# cam_switch_nobec.net
KiCad netlist of a schematic drawn in EAGLE
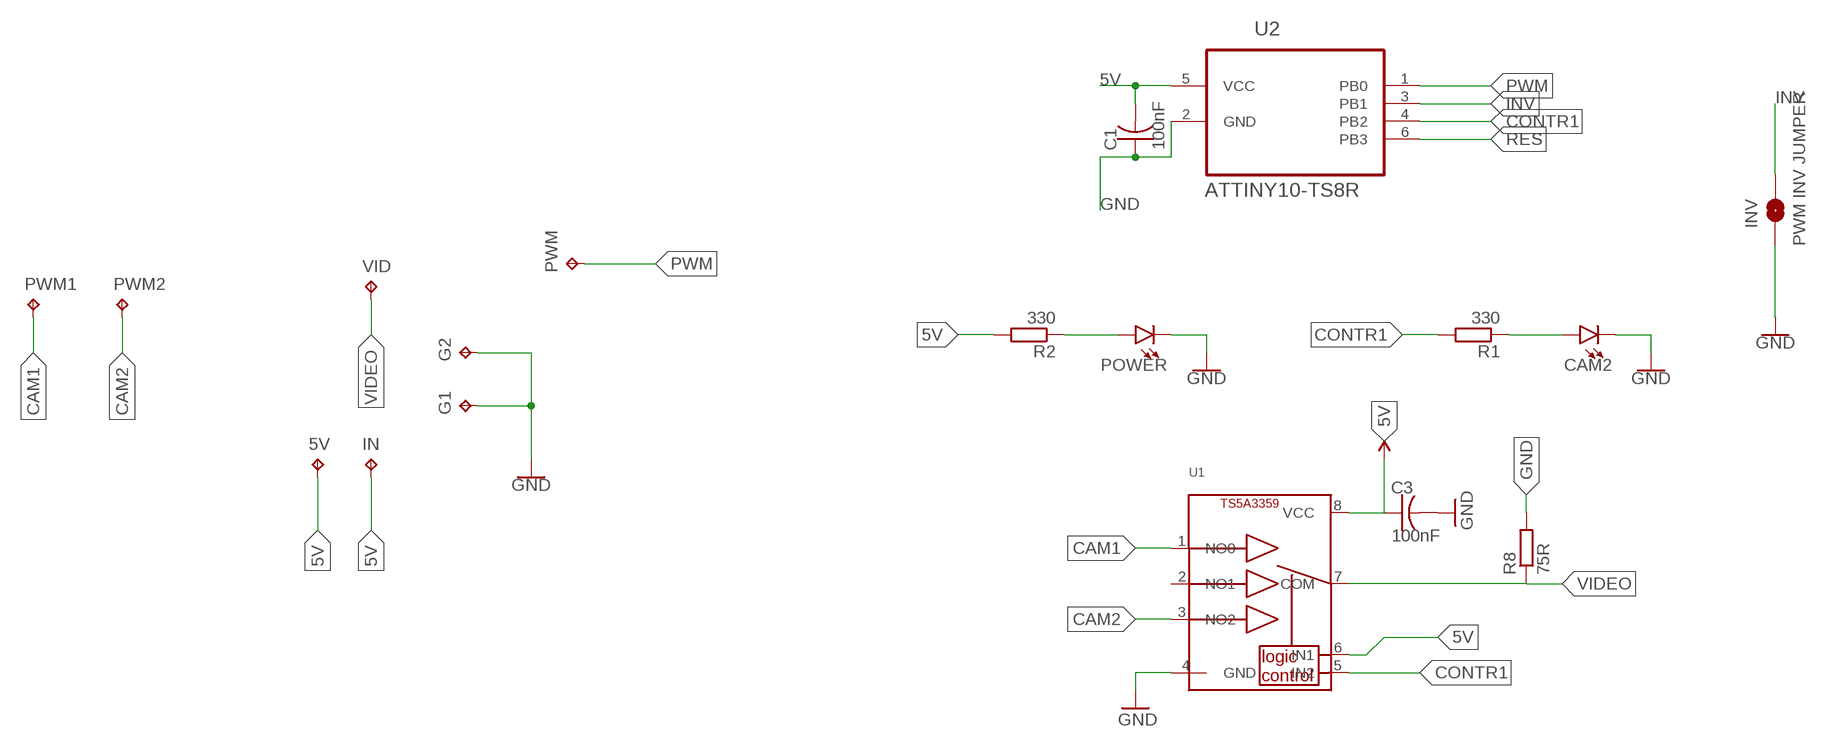
[diagram p0: schematic, sheet 1]

(export (version "E")
  (design (tool "Eeschema 10.0.6"))
  (components
    (comp (ref "5V")
      (value "TPTP20SQ")
      (footprint "eagle-import:TP20SQ")
      (libsource (lib "eagle-import") (part "TPTP20SQ"))
    )
    (comp (ref "C1")
      (value "100nF")
      (footprint "eagle-import:C0603")
      (libsource (lib "eagle-import") (part "C-USC0603"))
    )
    (comp (ref "C3")
      (value "100nF")
      (footprint "eagle-import:C0603")
      (libsource (lib "eagle-import") (part "C-USC0603"))
    )
    (comp (ref "CAM2")
      (value "LED0603")
      (footprint "eagle-import:LED-0603")
      (libsource (lib "eagle-import") (part "LED0603"))
    )
    (comp (ref "G1")
      (value "TPTP20SQ")
      (footprint "eagle-import:TP20SQ")
      (libsource (lib "eagle-import") (part "TPTP20SQ"))
    )
    (comp (ref "G2")
      (value "TPTP20SQ")
      (footprint "eagle-import:TP20SQ")
      (libsource (lib "eagle-import") (part "TPTP20SQ"))
    )
    (comp (ref "IN")
      (value "TPTP20SQ")
      (footprint "eagle-import:TP20SQ")
      (libsource (lib "eagle-import") (part "TPTP20SQ"))
    )
    (comp (ref "INV")
      (value "PWM INV JUMPER")
      (footprint "eagle-import:SMT-JUMPER_2_NO_NO-SILK")
      (libsource (lib "eagle-import") (part "JUMPER-SMT_2_NO_NO-SILK"))
    )
    (comp (ref "POWER")
      (value "LED0603")
      (footprint "eagle-import:LED-0603")
      (libsource (lib "eagle-import") (part "LED0603"))
    )
    (comp (ref "PWM")
      (value "TPTP20SQ")
      (footprint "eagle-import:TP20SQ")
      (libsource (lib "eagle-import") (part "TPTP20SQ"))
    )
    (comp (ref "PWM1")
      (value "TPTP20SQ")
      (footprint "eagle-import:TP20SQ")
      (libsource (lib "eagle-import") (part "TPTP20SQ"))
    )
    (comp (ref "PWM2")
      (value "TPTP20SQ")
      (footprint "eagle-import:TP20SQ")
      (libsource (lib "eagle-import") (part "TPTP20SQ"))
    )
    (comp (ref "R1")
      (value "330")
      (footprint "eagle-import:R0603")
      (libsource (lib "eagle-import") (part "R-EU_R0603"))
    )
    (comp (ref "R2")
      (value "330")
      (footprint "eagle-import:R0603")
      (libsource (lib "eagle-import") (part "R-EU_R0603"))
    )
    (comp (ref "R8")
      (value "75R")
      (footprint "eagle-import:R0603")
      (libsource (lib "eagle-import") (part "R-EU_R0603"))
    )
    (comp (ref "U1")
      (value "TS5A3359")
      (footprint "eagle-import:VFSOP-8")
      (libsource (lib "eagle-import") (part "TS5A3359"))
    )
    (comp (ref "U2")
      (value "ATTINY10-TS8R")
      (footprint "eagle-import:SOT95P280X145-6N")
      (fields (field (name "MF") "Microchip"))
      (libsource (lib "eagle-import") (part "ATTINY10-TS8R"))
    )
    (comp (ref "VID")
      (value "TPTP20SQ")
      (footprint "eagle-import:TP20SQ")
      (libsource (lib "eagle-import") (part "TPTP20SQ"))
    )
  )
  (nets
    (net (code "1") (name "5V") (class "Default")
      (node (ref "5V") (pin "TP") (pinfunction "TP_TP") (pintype "input"))
      (node (ref "C1") (pin "2") (pinfunction "2_2") (pintype "passive"))
      (node (ref "C3") (pin "1") (pinfunction "1_1") (pintype "passive"))
      (node (ref "IN") (pin "TP") (pinfunction "TP_TP") (pintype "input"))
      (node (ref "R2") (pin "2") (pinfunction "2_2") (pintype "passive"))
      (node (ref "U1") (pin "6") (pinfunction "IN1_6") (pintype "output"))
      (node (ref "U1") (pin "8") (pinfunction "VCC_8") (pintype "power_in"))
      (node (ref "U2") (pin "5") (pinfunction "VCC_5") (pintype "power_in"))
    )
    (net (code "2") (name "CAM1") (class "Default")
      (node (ref "PWM1") (pin "TP") (pinfunction "TP_TP") (pintype "input"))
      (node (ref "U1") (pin "1") (pinfunction "NO0_1") (pintype "input"))
    )
    (net (code "3") (name "CAM2") (class "Default")
      (node (ref "PWM2") (pin "TP") (pinfunction "TP_TP") (pintype "input"))
      (node (ref "U1") (pin "3") (pinfunction "NO2_3") (pintype "input"))
    )
    (net (code "4") (name "CONTR1") (class "Default")
      (node (ref "R1") (pin "2") (pinfunction "2_2") (pintype "passive"))
      (node (ref "U1") (pin "5") (pinfunction "IN2_5") (pintype "output"))
      (node (ref "U2") (pin "4") (pinfunction "PB2_4") (pintype "bidirectional"))
    )
    (net (code "5") (name "GND") (class "Default")
      (node (ref "C1") (pin "1") (pinfunction "1_1") (pintype "passive"))
      (node (ref "C3") (pin "2") (pinfunction "2_2") (pintype "passive"))
      (node (ref "CAM2") (pin "C") (pinfunction "C_C") (pintype "passive"))
      (node (ref "G1") (pin "TP") (pinfunction "TP_TP") (pintype "input"))
      (node (ref "G2") (pin "TP") (pinfunction "TP_TP") (pintype "input"))
      (node (ref "INV") (pin "1") (pinfunction "1_1") (pintype "passive"))
      (node (ref "POWER") (pin "C") (pinfunction "C_C") (pintype "passive"))
      (node (ref "R8") (pin "2") (pinfunction "2_2") (pintype "passive"))
      (node (ref "U1") (pin "4") (pinfunction "GND_4") (pintype "power_in"))
      (node (ref "U2") (pin "2") (pinfunction "GND_2") (pintype "passive"))
    )
    (net (code "6") (name "INV") (class "Default")
      (node (ref "INV") (pin "2") (pinfunction "2_2") (pintype "passive"))
      (node (ref "U2") (pin "3") (pinfunction "PB1_3") (pintype "bidirectional"))
    )
    (net (code "7") (name "Net-(CAM2-PadA)") (class "Default")
      (node (ref "CAM2") (pin "A") (pinfunction "A_A") (pintype "passive"))
      (node (ref "R1") (pin "1") (pinfunction "1_1") (pintype "passive"))
    )
    (net (code "8") (name "Net-(POWER-PadA)") (class "Default")
      (node (ref "POWER") (pin "A") (pinfunction "A_A") (pintype "passive"))
      (node (ref "R2") (pin "1") (pinfunction "1_1") (pintype "passive"))
    )
    (net (code "9") (name "PWM") (class "Default")
      (node (ref "PWM") (pin "TP") (pinfunction "TP_TP") (pintype "input"))
      (node (ref "U2") (pin "1") (pinfunction "PB0_1") (pintype "bidirectional"))
    )
    (net (code "10") (name "RES") (class "Default")
      (node (ref "U2") (pin "6") (pinfunction "PB3_6") (pintype "bidirectional"))
    )
    (net (code "11") (name "VIDEO") (class "Default")
      (node (ref "R8") (pin "1") (pinfunction "1_1") (pintype "passive"))
      (node (ref "U1") (pin "7") (pinfunction "COM_7") (pintype "input"))
      (node (ref "VID") (pin "TP") (pinfunction "TP_TP") (pintype "input"))
    )
    (net (code "12") (name "unconnected-(U1-NO1-Pad2)") (class "Default")
      (node (ref "U1") (pin "2") (pinfunction "NO1_2") (pintype "input"))
    )
  )
)
